# rpi.net
KiCad netlist of a schematic drawn in EAGLE
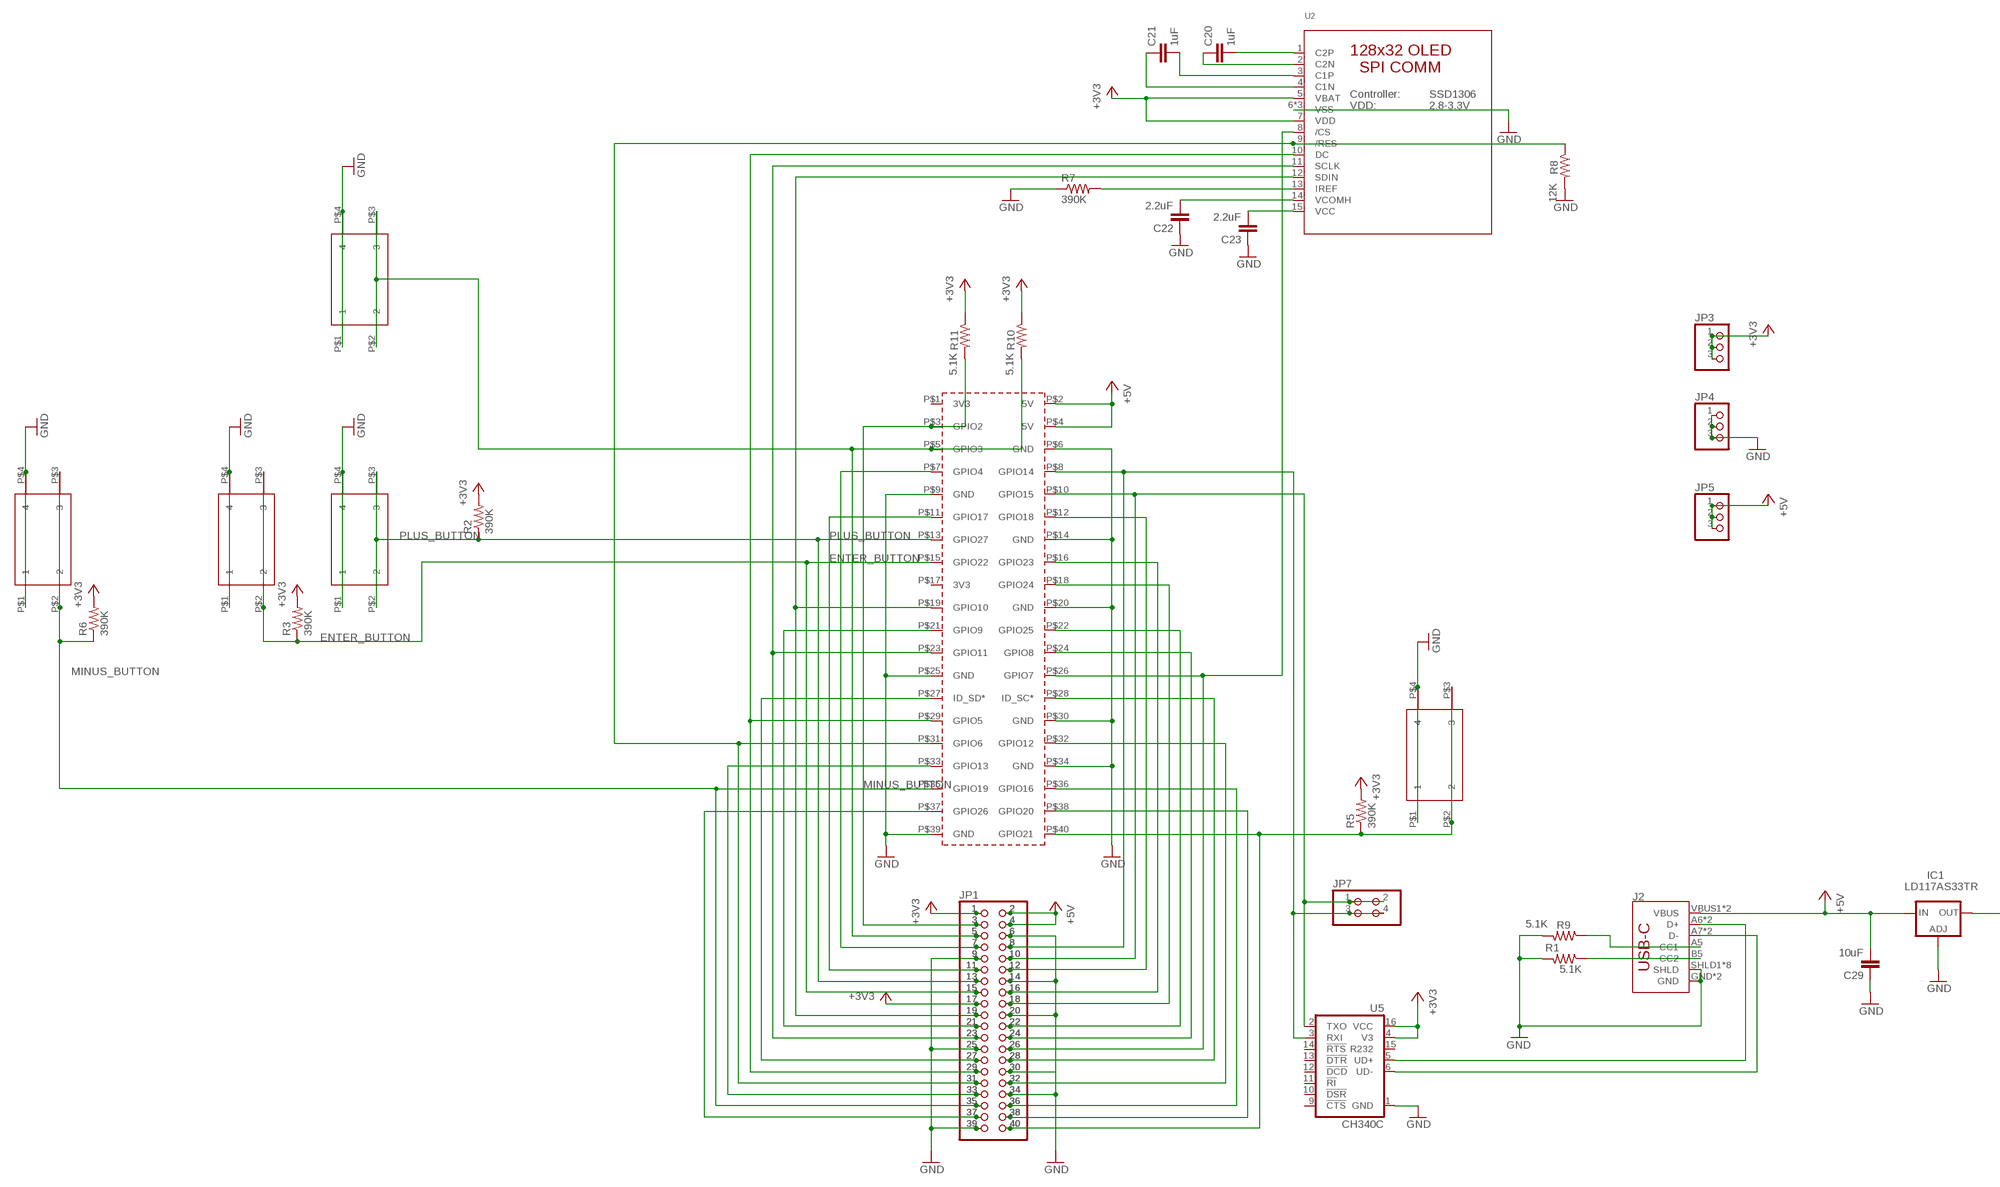
[diagram p0: schematic, sheet 1, part 1 of 2]
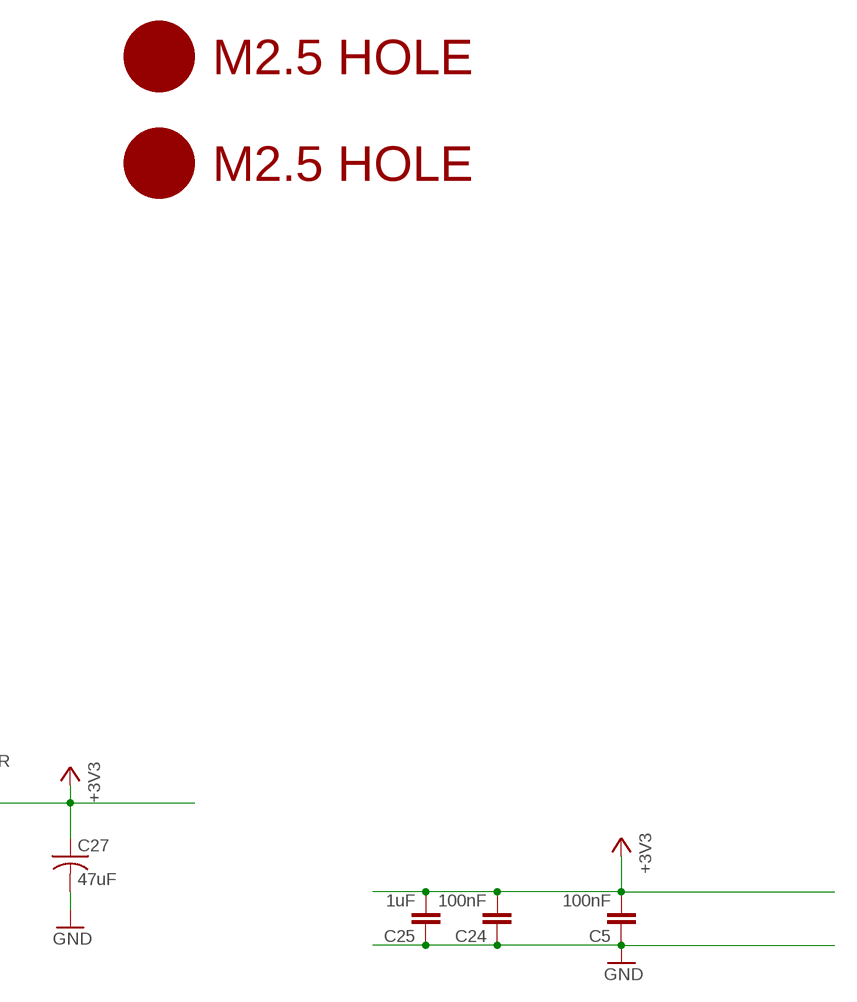
[diagram p1: schematic, sheet 1, part 2 of 2]

(export (version "E")
  (design (tool "Eeschema 10.0.6"))
  (components
    (comp (ref "C5")
      (value "100nF")
      (footprint "eagle-import:0805")
      (libsource (lib "eagle-import") (part "CAP0805"))
    )
    (comp (ref "C20")
      (value "1uF")
      (footprint "eagle-import:0805")
      (libsource (lib "eagle-import") (part "CAP0805"))
    )
    (comp (ref "C21")
      (value "1uF")
      (footprint "eagle-import:0805")
      (libsource (lib "eagle-import") (part "CAP0805"))
    )
    (comp (ref "C22")
      (value "2.2uF")
      (footprint "eagle-import:0805")
      (libsource (lib "eagle-import") (part "CAP0805"))
    )
    (comp (ref "C23")
      (value "2.2uF")
      (footprint "eagle-import:0805")
      (libsource (lib "eagle-import") (part "CAP0805"))
    )
    (comp (ref "C24")
      (value "100nF")
      (footprint "eagle-import:0805")
      (libsource (lib "eagle-import") (part "CAP0805"))
    )
    (comp (ref "C25")
      (value "1uF")
      (footprint "eagle-import:0805")
      (libsource (lib "eagle-import") (part "CAP0805"))
    )
    (comp (ref "C27")
      (value "47uF")
      (footprint "eagle-import:C1210")
      (libsource (lib "eagle-import") (part "C-USC1210"))
    )
    (comp (ref "C29")
      (value "10uF")
      (footprint "eagle-import:0805")
      (libsource (lib "eagle-import") (part "CAP0805"))
    )
    (comp (ref "IC1")
      (value "LD117AS33TR")
      (footprint "eagle-import:SOT223")
      (libsource (lib "eagle-import") (part "LD117A?S33TR"))
    )
    (comp (ref "J2")
      (value "USB_C16PIN")
      (footprint "eagle-import:USB-C-16P")
      (libsource (lib "eagle-import") (part "USB_C16PIN"))
    )
    (comp (ref "JP1")
      (value "PINHD-2X20-BIG")
      (footprint "eagle-import:2X20-BIG")
      (libsource (lib "eagle-import") (part "PINHD-2X20-BIG"))
    )
    (comp (ref "JP2")
      (value "PINHD-2X20-BIG")
      (footprint "eagle-import:2X20-BIG")
      (libsource (lib "eagle-import") (part "PINHD-2X20-BIG"))
    )
    (comp (ref "JP3")
      (value "PINHD-1X3")
      (footprint "eagle-import:1X03")
      (libsource (lib "eagle-import") (part "PINHD-1X3"))
    )
    (comp (ref "JP4")
      (value "PINHD-1X3")
      (footprint "eagle-import:1X03")
      (libsource (lib "eagle-import") (part "PINHD-1X3"))
    )
    (comp (ref "JP5")
      (value "PINHD-1X3")
      (footprint "eagle-import:1X03")
      (libsource (lib "eagle-import") (part "PINHD-1X3"))
    )
    (comp (ref "JP7")
      (value "PINHD-2X2")
      (footprint "eagle-import:2X02")
      (libsource (lib "eagle-import") (part "PINHD-2X2"))
    )
    (comp (ref "PCB1")
      (value "RPI3NO-CONNECTORS")
      (footprint "eagle-import:RPI3-NO-CONNECTORS")
      (libsource (lib "eagle-import") (part "RPI3NO-CONNECTORS"))
    )
    (comp (ref "R1")
      (value "5.1K")
      (footprint "eagle-import:0805")
      (libsource (lib "eagle-import") (part "joyAnalog_RESISTOR0805-RES"))
    )
    (comp (ref "R2")
      (value "390K")
      (footprint "eagle-import:0805")
      (libsource (lib "eagle-import") (part "RESISTOR0805-RES"))
    )
    (comp (ref "R3")
      (value "390K")
      (footprint "eagle-import:0805")
      (libsource (lib "eagle-import") (part "RESISTOR0805-RES"))
    )
    (comp (ref "R5")
      (value "390K")
      (footprint "eagle-import:0805")
      (libsource (lib "eagle-import") (part "RESISTOR0805-RES"))
    )
    (comp (ref "R6")
      (value "390K")
      (footprint "eagle-import:0805")
      (libsource (lib "eagle-import") (part "RESISTOR0805-RES"))
    )
    (comp (ref "R7")
      (value "390K")
      (footprint "eagle-import:0805")
      (libsource (lib "eagle-import") (part "RESISTOR0805-RES"))
    )
    (comp (ref "R8")
      (value "12K")
      (footprint "eagle-import:0805")
      (libsource (lib "eagle-import") (part "joyAnalog_RESISTOR0805-RES"))
    )
    (comp (ref "R9")
      (value "5.1K")
      (footprint "eagle-import:0805")
      (libsource (lib "eagle-import") (part "joyAnalog_RESISTOR0805-RES"))
    )
    (comp (ref "R10")
      (value "5.1K")
      (footprint "eagle-import:0805")
      (libsource (lib "eagle-import") (part "joyAnalog_RESISTOR0805-RES"))
    )
    (comp (ref "R11")
      (value "5.1K")
      (footprint "eagle-import:0805")
      (libsource (lib "eagle-import") (part "joyAnalog_RESISTOR0805-RES"))
    )
    (comp (ref "SW1")
      (value "324_SW")
      (footprint "eagle-import:342_SWICH_FOOT")
      (libsource (lib "eagle-import") (part "324_SW"))
    )
    (comp (ref "SW2")
      (value "324_SW")
      (footprint "eagle-import:342_SWICH_FOOT")
      (libsource (lib "eagle-import") (part "324_SW"))
    )
    (comp (ref "SW3")
      (value "324_SW")
      (footprint "eagle-import:342_SWICH_FOOT")
      (libsource (lib "eagle-import") (part "324_SW"))
    )
    (comp (ref "SW4")
      (value "324_SW")
      (footprint "eagle-import:342_SWICH_FOOT")
      (libsource (lib "eagle-import") (part "324_SW"))
    )
    (comp (ref "SW20")
      (value "324_SW")
      (footprint "eagle-import:342_SWICH_FOOT")
      (libsource (lib "eagle-import") (part "324_SW"))
    )
    (comp (ref "U$2")
      (value "M2.5HOLE")
      (footprint "eagle-import:M2.5HOLE")
      (libsource (lib "eagle-import") (part "M2.5HOLE"))
    )
    (comp (ref "U$3")
      (value "M2.5HOLE")
      (footprint "eagle-import:M2.5HOLE")
      (libsource (lib "eagle-import") (part "M2.5HOLE"))
    )
    (comp (ref "U2")
      (value "LUL_DISP_OLED_UG-2864HSWEG01")
      (footprint "eagle-import:LUL_UG-2864HSWEG01_1.3_WRAPAROUND")
      (libsource (lib "eagle-import") (part "LUL_DISP_OLED_UG-2864HSWEG01"))
    )
    (comp (ref "U5")
      (value "CH340C")
      (footprint "eagle-import:SO016")
      (libsource (lib "eagle-import") (part "CH340C"))
    )
  )
  (nets
    (net (code "1") (name "+3V3") (class "Default")
      (node (ref "C24") (pin "2") (pinfunction "2_2") (pintype "passive"))
      (node (ref "C25") (pin "2") (pinfunction "2_2") (pintype "passive"))
      (node (ref "C27") (pin "1") (pinfunction "1_1") (pintype "passive"))
      (node (ref "C5") (pin "2") (pinfunction "2_2") (pintype "passive"))
      (node (ref "IC1") (pin "4") (pinfunction "OUT_4") (pintype "passive"))
      (node (ref "JP1") (pin "1") (pinfunction "1_1") (pintype "passive"))
      (node (ref "JP1") (pin "17") (pinfunction "17_17") (pintype "passive"))
      (node (ref "JP2") (pin "1") (pinfunction "1_1") (pintype "passive"))
      (node (ref "JP2") (pin "17") (pinfunction "17_17") (pintype "passive"))
      (node (ref "JP3") (pin "1") (pinfunction "1_1") (pintype "passive"))
      (node (ref "JP3") (pin "2") (pinfunction "2_2") (pintype "passive"))
      (node (ref "JP3") (pin "3") (pinfunction "3_3") (pintype "passive"))
      (node (ref "R10") (pin "1") (pinfunction "1_1") (pintype "passive"))
      (node (ref "R11") (pin "1") (pinfunction "1_1") (pintype "passive"))
      (node (ref "R2") (pin "2") (pinfunction "2_2") (pintype "passive"))
      (node (ref "R3") (pin "2") (pinfunction "2_2") (pintype "passive"))
      (node (ref "R5") (pin "2") (pinfunction "2_2") (pintype "passive"))
      (node (ref "R6") (pin "2") (pinfunction "2_2") (pintype "passive"))
      (node (ref "U2") (pin "5") (pinfunction "VBAT_5") (pintype "input"))
      (node (ref "U2") (pin "7") (pinfunction "VDD_7") (pintype "power_in"))
      (node (ref "U5") (pin "16") (pinfunction "VCC_16") (pintype "bidirectional"))
      (node (ref "U5") (pin "4") (pinfunction "V3_4") (pintype "bidirectional"))
    )
    (net (code "2") (name "+5V") (class "Default")
      (node (ref "C29") (pin "2") (pinfunction "2_2") (pintype "passive"))
      (node (ref "IC1") (pin "3") (pinfunction "IN_3") (pintype "input"))
      (node (ref "J2") (pin "VBUS1") (pinfunction "VBUS_VBUS1") (pintype "bidirectional"))
      (node (ref "J2") (pin "VBUS2") (pinfunction "VBUS_VBUS2") (pintype "bidirectional"))
      (node (ref "JP1") (pin "2") (pinfunction "2_2") (pintype "passive"))
      (node (ref "JP1") (pin "4") (pinfunction "4_4") (pintype "passive"))
      (node (ref "JP2") (pin "2") (pinfunction "2_2") (pintype "passive"))
      (node (ref "JP2") (pin "4") (pinfunction "4_4") (pintype "passive"))
      (node (ref "JP5") (pin "1") (pinfunction "1_1") (pintype "passive"))
      (node (ref "JP5") (pin "2") (pinfunction "2_2") (pintype "passive"))
      (node (ref "JP5") (pin "3") (pinfunction "3_3") (pintype "passive"))
      (node (ref "PCB1") (pin "P$2") (pinfunction "5V_P$2") (pintype "bidirectional"))
      (node (ref "PCB1") (pin "P$4") (pinfunction "5V_P$4") (pintype "bidirectional"))
    )
    (net (code "3") (name "/ENTER_BUTTON") (class "Default")
      (node (ref "JP1") (pin "15") (pinfunction "15_15") (pintype "passive"))
      (node (ref "JP2") (pin "15") (pinfunction "15_15") (pintype "passive"))
      (node (ref "PCB1") (pin "P$15") (pinfunction "GPIO22_P$15") (pintype "bidirectional"))
      (node (ref "R3") (pin "1") (pinfunction "1_1") (pintype "passive"))
      (node (ref "SW20") (pin "P$2") (pinfunction "2_P$2") (pintype "bidirectional"))
      (node (ref "SW20") (pin "P$3") (pinfunction "3_P$3") (pintype "bidirectional"))
    )
    (net (code "4") (name "/MINUS_BUTTON") (class "Default")
      (node (ref "JP1") (pin "35") (pinfunction "35_35") (pintype "passive"))
      (node (ref "JP2") (pin "35") (pinfunction "35_35") (pintype "passive"))
      (node (ref "PCB1") (pin "P$35") (pinfunction "GPIO19_P$35") (pintype "bidirectional"))
      (node (ref "R6") (pin "1") (pinfunction "1_1") (pintype "passive"))
      (node (ref "SW4") (pin "P$2") (pinfunction "2_P$2") (pintype "bidirectional"))
      (node (ref "SW4") (pin "P$3") (pinfunction "3_P$3") (pintype "bidirectional"))
    )
    (net (code "5") (name "/PLUS_BUTTON") (class "Default")
      (node (ref "JP1") (pin "13") (pinfunction "13_13") (pintype "passive"))
      (node (ref "JP2") (pin "13") (pinfunction "13_13") (pintype "passive"))
      (node (ref "PCB1") (pin "P$13") (pinfunction "GPIO27_P$13") (pintype "bidirectional"))
      (node (ref "R2") (pin "1") (pinfunction "1_1") (pintype "passive"))
      (node (ref "SW1") (pin "P$2") (pinfunction "2_P$2") (pintype "bidirectional"))
      (node (ref "SW1") (pin "P$3") (pinfunction "3_P$3") (pintype "bidirectional"))
    )
    (net (code "6") (name "GND") (class "Default")
      (node (ref "C22") (pin "1") (pinfunction "1_1") (pintype "passive"))
      (node (ref "C23") (pin "1") (pinfunction "1_1") (pintype "passive"))
      (node (ref "C24") (pin "1") (pinfunction "1_1") (pintype "passive"))
      (node (ref "C25") (pin "1") (pinfunction "1_1") (pintype "passive"))
      (node (ref "C27") (pin "2") (pinfunction "2_2") (pintype "passive"))
      (node (ref "C29") (pin "1") (pinfunction "1_1") (pintype "passive"))
      (node (ref "C5") (pin "1") (pinfunction "1_1") (pintype "passive"))
      (node (ref "IC1") (pin "1") (pinfunction "ADJ_1") (pintype "input"))
      (node (ref "J2") (pin "GND") (pinfunction "GND_GND") (pintype "bidirectional"))
      (node (ref "J2") (pin "GND2") (pinfunction "GND_GND2") (pintype "bidirectional"))
      (node (ref "J2") (pin "SHLD1") (pinfunction "SHLD_SHLD1") (pintype "bidirectional"))
      (node (ref "J2") (pin "SHLD2") (pinfunction "SHLD_SHLD2") (pintype "bidirectional"))
      (node (ref "J2") (pin "SHLD3") (pinfunction "SHLD_SHLD3") (pintype "bidirectional"))
      (node (ref "J2") (pin "SHLD4") (pinfunction "SHLD_SHLD4") (pintype "bidirectional"))
      (node (ref "J2") (pin "SHLD5") (pinfunction "SHLD_SHLD5") (pintype "bidirectional"))
      (node (ref "J2") (pin "SHLD6") (pinfunction "SHLD_SHLD6") (pintype "bidirectional"))
      (node (ref "J2") (pin "SHLD7") (pinfunction "SHLD_SHLD7") (pintype "bidirectional"))
      (node (ref "J2") (pin "SHLD8") (pinfunction "SHLD_SHLD8") (pintype "bidirectional"))
      (node (ref "JP1") (pin "14") (pinfunction "14_14") (pintype "passive"))
      (node (ref "JP1") (pin "20") (pinfunction "20_20") (pintype "passive"))
      (node (ref "JP1") (pin "25") (pinfunction "25_25") (pintype "passive"))
      (node (ref "JP1") (pin "30") (pinfunction "30_30") (pintype "passive"))
      (node (ref "JP1") (pin "34") (pinfunction "34_34") (pintype "passive"))
      (node (ref "JP1") (pin "39") (pinfunction "39_39") (pintype "passive"))
      (node (ref "JP1") (pin "6") (pinfunction "6_6") (pintype "passive"))
      (node (ref "JP1") (pin "9") (pinfunction "9_9") (pintype "passive"))
      (node (ref "JP2") (pin "14") (pinfunction "14_14") (pintype "passive"))
      (node (ref "JP2") (pin "20") (pinfunction "20_20") (pintype "passive"))
      (node (ref "JP2") (pin "25") (pinfunction "25_25") (pintype "passive"))
      (node (ref "JP2") (pin "30") (pinfunction "30_30") (pintype "passive"))
      (node (ref "JP2") (pin "34") (pinfunction "34_34") (pintype "passive"))
      (node (ref "JP2") (pin "39") (pinfunction "39_39") (pintype "passive"))
      (node (ref "JP2") (pin "6") (pinfunction "6_6") (pintype "passive"))
      (node (ref "JP2") (pin "9") (pinfunction "9_9") (pintype "passive"))
      (node (ref "JP4") (pin "1") (pinfunction "1_1") (pintype "passive"))
      (node (ref "JP4") (pin "2") (pinfunction "2_2") (pintype "passive"))
      (node (ref "JP4") (pin "3") (pinfunction "3_3") (pintype "passive"))
      (node (ref "PCB1") (pin "P$14") (pinfunction "GND_P$14") (pintype "bidirectional"))
      (node (ref "PCB1") (pin "P$20") (pinfunction "GND_P$20") (pintype "bidirectional"))
      (node (ref "PCB1") (pin "P$25") (pinfunction "GND_P$25") (pintype "bidirectional"))
      (node (ref "PCB1") (pin "P$30") (pinfunction "GND_P$30") (pintype "bidirectional"))
      (node (ref "PCB1") (pin "P$34") (pinfunction "GND_P$34") (pintype "bidirectional"))
      (node (ref "PCB1") (pin "P$39") (pinfunction "GND_P$39") (pintype "bidirectional"))
      (node (ref "PCB1") (pin "P$6") (pinfunction "GND_P$6") (pintype "bidirectional"))
      (node (ref "PCB1") (pin "P$9") (pinfunction "GND_P$9") (pintype "bidirectional"))
      (node (ref "R1") (pin "2") (pinfunction "2_2") (pintype "passive"))
      (node (ref "R7") (pin "1") (pinfunction "1_1") (pintype "passive"))
      (node (ref "R8") (pin "2") (pinfunction "2_2") (pintype "passive"))
      (node (ref "R9") (pin "2") (pinfunction "2_2") (pintype "passive"))
      (node (ref "SW1") (pin "P$1") (pinfunction "1_P$1") (pintype "bidirectional"))
      (node (ref "SW1") (pin "P$4") (pinfunction "4_P$4") (pintype "bidirectional"))
      (node (ref "SW2") (pin "P$1") (pinfunction "1_P$1") (pintype "bidirectional"))
      (node (ref "SW2") (pin "P$4") (pinfunction "4_P$4") (pintype "bidirectional"))
      (node (ref "SW20") (pin "P$1") (pinfunction "1_P$1") (pintype "bidirectional"))
      (node (ref "SW20") (pin "P$4") (pinfunction "4_P$4") (pintype "bidirectional"))
      (node (ref "SW3") (pin "P$1") (pinfunction "1_P$1") (pintype "bidirectional"))
      (node (ref "SW3") (pin "P$4") (pinfunction "4_P$4") (pintype "bidirectional"))
      (node (ref "SW4") (pin "P$1") (pinfunction "1_P$1") (pintype "bidirectional"))
      (node (ref "SW4") (pin "P$4") (pinfunction "4_P$4") (pintype "bidirectional"))
      (node (ref "U2") (pin "16") (pinfunction "VSS_16") (pintype "power_in"))
      (node (ref "U2") (pin "17") (pinfunction "VSS_17") (pintype "power_in"))
      (node (ref "U2") (pin "6") (pinfunction "VSS_6") (pintype "power_in"))
      (node (ref "U5") (pin "1") (pinfunction "GND_1") (pintype "bidirectional"))
    )
    (net (code "7") (name "Net-(J2-CC1)") (class "Default")
      (node (ref "J2") (pin "A5") (pinfunction "CC1_A5") (pintype "bidirectional"))
      (node (ref "R9") (pin "1") (pinfunction "1_1") (pintype "passive"))
    )
    (net (code "8") (name "Net-(J2-CC2)") (class "Default")
      (node (ref "J2") (pin "B5") (pinfunction "CC2_B5") (pintype "bidirectional"))
      (node (ref "R1") (pin "1") (pinfunction "1_1") (pintype "passive"))
    )
    (net (code "9") (name "Net-(PCB1-GPIO2)") (class "Default")
      (node (ref "JP1") (pin "3") (pinfunction "3_3") (pintype "passive"))
      (node (ref "JP2") (pin "3") (pinfunction "3_3") (pintype "passive"))
      (node (ref "PCB1") (pin "P$3") (pinfunction "GPIO2_P$3") (pintype "bidirectional"))
      (node (ref "R11") (pin "2") (pinfunction "2_2") (pintype "passive"))
    )
    (net (code "10") (name "Net-(PCB1-GPIO3)") (class "Default")
      (node (ref "JP1") (pin "5") (pinfunction "5_5") (pintype "passive"))
      (node (ref "JP2") (pin "5") (pinfunction "5_5") (pintype "passive"))
      (node (ref "PCB1") (pin "P$5") (pinfunction "GPIO3_P$5") (pintype "bidirectional"))
      (node (ref "R10") (pin "2") (pinfunction "2_2") (pintype "passive"))
      (node (ref "SW2") (pin "P$2") (pinfunction "2_P$2") (pintype "bidirectional"))
      (node (ref "SW2") (pin "P$3") (pinfunction "3_P$3") (pintype "bidirectional"))
    )
    (net (code "11") (name "Net-(PCB1-GPIO4)") (class "Default")
      (node (ref "JP1") (pin "7") (pinfunction "7_7") (pintype "passive"))
      (node (ref "JP2") (pin "7") (pinfunction "7_7") (pintype "passive"))
      (node (ref "PCB1") (pin "P$7") (pinfunction "GPIO4_P$7") (pintype "bidirectional"))
    )
    (net (code "12") (name "Net-(PCB1-GPIO5)") (class "Default")
      (node (ref "JP1") (pin "29") (pinfunction "29_29") (pintype "passive"))
      (node (ref "JP2") (pin "29") (pinfunction "29_29") (pintype "passive"))
      (node (ref "PCB1") (pin "P$29") (pinfunction "GPIO5_P$29") (pintype "bidirectional"))
      (node (ref "U2") (pin "10") (pinfunction "DC_10") (pintype "input"))
    )
    (net (code "13") (name "Net-(PCB1-GPIO6)") (class "Default")
      (node (ref "JP1") (pin "31") (pinfunction "31_31") (pintype "passive"))
      (node (ref "JP2") (pin "31") (pinfunction "31_31") (pintype "passive"))
      (node (ref "PCB1") (pin "P$31") (pinfunction "GPIO6_P$31") (pintype "bidirectional"))
      (node (ref "R8") (pin "1") (pinfunction "1_1") (pintype "passive"))
      (node (ref "U2") (pin "9") (pinfunction "/RES_9") (pintype "input"))
    )
    (net (code "14") (name "Net-(PCB1-GPIO7)") (class "Default")
      (node (ref "JP1") (pin "26") (pinfunction "26_26") (pintype "passive"))
      (node (ref "JP2") (pin "26") (pinfunction "26_26") (pintype "passive"))
      (node (ref "PCB1") (pin "P$26") (pinfunction "GPIO7_P$26") (pintype "bidirectional"))
      (node (ref "U2") (pin "8") (pinfunction "/CS_8") (pintype "input"))
    )
    (net (code "15") (name "Net-(PCB1-GPIO8)") (class "Default")
      (node (ref "JP1") (pin "24") (pinfunction "24_24") (pintype "passive"))
      (node (ref "JP2") (pin "24") (pinfunction "24_24") (pintype "passive"))
      (node (ref "PCB1") (pin "P$24") (pinfunction "GPIO8_P$24") (pintype "bidirectional"))
    )
    (net (code "16") (name "Net-(PCB1-GPIO9)") (class "Default")
      (node (ref "JP1") (pin "21") (pinfunction "21_21") (pintype "passive"))
      (node (ref "JP2") (pin "21") (pinfunction "21_21") (pintype "passive"))
      (node (ref "PCB1") (pin "P$21") (pinfunction "GPIO9_P$21") (pintype "bidirectional"))
    )
    (net (code "17") (name "Net-(PCB1-GPIO10)") (class "Default")
      (node (ref "JP1") (pin "19") (pinfunction "19_19") (pintype "passive"))
      (node (ref "JP2") (pin "19") (pinfunction "19_19") (pintype "passive"))
      (node (ref "PCB1") (pin "P$19") (pinfunction "GPIO10_P$19") (pintype "bidirectional"))
      (node (ref "U2") (pin "12") (pinfunction "SDIN_12") (pintype "bidirectional"))
    )
    (net (code "18") (name "Net-(PCB1-GPIO11)") (class "Default")
      (node (ref "JP1") (pin "23") (pinfunction "23_23") (pintype "passive"))
      (node (ref "JP2") (pin "23") (pinfunction "23_23") (pintype "passive"))
      (node (ref "PCB1") (pin "P$23") (pinfunction "GPIO11_P$23") (pintype "bidirectional"))
      (node (ref "U2") (pin "11") (pinfunction "SCLK_11") (pintype "bidirectional"))
    )
    (net (code "19") (name "Net-(PCB1-GPIO12)") (class "Default")
      (node (ref "JP1") (pin "32") (pinfunction "32_32") (pintype "passive"))
      (node (ref "JP2") (pin "32") (pinfunction "32_32") (pintype "passive"))
      (node (ref "PCB1") (pin "P$32") (pinfunction "GPIO12_P$32") (pintype "bidirectional"))
    )
    (net (code "20") (name "Net-(PCB1-GPIO13)") (class "Default")
      (node (ref "JP1") (pin "33") (pinfunction "33_33") (pintype "passive"))
      (node (ref "JP2") (pin "33") (pinfunction "33_33") (pintype "passive"))
      (node (ref "PCB1") (pin "P$33") (pinfunction "GPIO13_P$33") (pintype "bidirectional"))
    )
    (net (code "21") (name "Net-(PCB1-GPIO14)") (class "Default")
      (node (ref "JP1") (pin "8") (pinfunction "8_8") (pintype "passive"))
      (node (ref "JP2") (pin "8") (pinfunction "8_8") (pintype "passive"))
      (node (ref "JP7") (pin "3") (pinfunction "3_3") (pintype "passive"))
      (node (ref "JP7") (pin "4") (pinfunction "4_4") (pintype "passive"))
      (node (ref "PCB1") (pin "P$8") (pinfunction "GPIO14_P$8") (pintype "bidirectional"))
      (node (ref "U5") (pin "3") (pinfunction "RXI_3") (pintype "bidirectional"))
    )
    (net (code "22") (name "Net-(PCB1-GPIO15)") (class "Default")
      (node (ref "JP1") (pin "10") (pinfunction "10_10") (pintype "passive"))
      (node (ref "JP2") (pin "10") (pinfunction "10_10") (pintype "passive"))
      (node (ref "JP7") (pin "1") (pinfunction "1_1") (pintype "passive"))
      (node (ref "JP7") (pin "2") (pinfunction "2_2") (pintype "passive"))
      (node (ref "PCB1") (pin "P$10") (pinfunction "GPIO15_P$10") (pintype "bidirectional"))
      (node (ref "U5") (pin "2") (pinfunction "TXO_2") (pintype "bidirectional"))
    )
    (net (code "23") (name "Net-(PCB1-GPIO16)") (class "Default")
      (node (ref "JP1") (pin "36") (pinfunction "36_36") (pintype "passive"))
      (node (ref "JP2") (pin "36") (pinfunction "36_36") (pintype "passive"))
      (node (ref "PCB1") (pin "P$36") (pinfunction "GPIO16_P$36") (pintype "bidirectional"))
    )
    (net (code "24") (name "Net-(PCB1-GPIO17)") (class "Default")
      (node (ref "JP1") (pin "11") (pinfunction "11_11") (pintype "passive"))
      (node (ref "JP2") (pin "11") (pinfunction "11_11") (pintype "passive"))
      (node (ref "PCB1") (pin "P$11") (pinfunction "GPIO17_P$11") (pintype "bidirectional"))
    )
    (net (code "25") (name "Net-(PCB1-GPIO18)") (class "Default")
      (node (ref "JP1") (pin "12") (pinfunction "12_12") (pintype "passive"))
      (node (ref "JP2") (pin "12") (pinfunction "12_12") (pintype "passive"))
      (node (ref "PCB1") (pin "P$12") (pinfunction "GPIO18_P$12") (pintype "bidirectional"))
    )
    (net (code "26") (name "Net-(PCB1-GPIO20)") (class "Default")
      (node (ref "JP1") (pin "38") (pinfunction "38_38") (pintype "passive"))
      (node (ref "JP2") (pin "38") (pinfunction "38_38") (pintype "passive"))
      (node (ref "PCB1") (pin "P$38") (pinfunction "GPIO20_P$38") (pintype "bidirectional"))
    )
    (net (code "27") (name "Net-(PCB1-GPIO21)") (class "Default")
      (node (ref "JP1") (pin "40") (pinfunction "40_40") (pintype "passive"))
      (node (ref "JP2") (pin "40") (pinfunction "40_40") (pintype "passive"))
      (node (ref "PCB1") (pin "P$40") (pinfunction "GPIO21_P$40") (pintype "bidirectional"))
      (node (ref "R5") (pin "1") (pinfunction "1_1") (pintype "passive"))
      (node (ref "SW3") (pin "P$2") (pinfunction "2_P$2") (pintype "bidirectional"))
      (node (ref "SW3") (pin "P$3") (pinfunction "3_P$3") (pintype "bidirectional"))
    )
    (net (code "28") (name "Net-(PCB1-GPIO23)") (class "Default")
      (node (ref "JP1") (pin "16") (pinfunction "16_16") (pintype "passive"))
      (node (ref "JP2") (pin "16") (pinfunction "16_16") (pintype "passive"))
      (node (ref "PCB1") (pin "P$16") (pinfunction "GPIO23_P$16") (pintype "bidirectional"))
    )
    (net (code "29") (name "Net-(PCB1-GPIO24)") (class "Default")
      (node (ref "JP1") (pin "18") (pinfunction "18_18") (pintype "passive"))
      (node (ref "JP2") (pin "18") (pinfunction "18_18") (pintype "passive"))
      (node (ref "PCB1") (pin "P$18") (pinfunction "GPIO24_P$18") (pintype "bidirectional"))
    )
    (net (code "30") (name "Net-(PCB1-GPIO25)") (class "Default")
      (node (ref "JP1") (pin "22") (pinfunction "22_22") (pintype "passive"))
      (node (ref "JP2") (pin "22") (pinfunction "22_22") (pintype "passive"))
      (node (ref "PCB1") (pin "P$22") (pinfunction "GPIO25_P$22") (pintype "bidirectional"))
    )
    (net (code "31") (name "Net-(PCB1-GPIO26)") (class "Default")
      (node (ref "JP1") (pin "37") (pinfunction "37_37") (pintype "passive"))
      (node (ref "JP2") (pin "37") (pinfunction "37_37") (pintype "passive"))
      (node (ref "PCB1") (pin "P$37") (pinfunction "GPIO26_P$37") (pintype "bidirectional"))
    )
    (net (code "32") (name "Net-(PCB1-ID_SC*)") (class "Default")
      (node (ref "JP1") (pin "28") (pinfunction "28_28") (pintype "passive"))
      (node (ref "JP2") (pin "28") (pinfunction "28_28") (pintype "passive"))
      (node (ref "PCB1") (pin "P$28") (pinfunction "ID_SC*_P$28") (pintype "bidirectional"))
    )
    (net (code "33") (name "Net-(PCB1-ID_SD*)") (class "Default")
      (node (ref "JP1") (pin "27") (pinfunction "27_27") (pintype "passive"))
      (node (ref "JP2") (pin "27") (pinfunction "27_27") (pintype "passive"))
      (node (ref "PCB1") (pin "P$27") (pinfunction "ID_SD*_P$27") (pintype "bidirectional"))
    )
    (net (code "34") (name "Net-(U2-C1N)") (class "Default")
      (node (ref "C21") (pin "1") (pinfunction "1_1") (pintype "passive"))
      (node (ref "U2") (pin "4") (pinfunction "C1N_4") (pintype "input"))
    )
    (net (code "35") (name "Net-(U2-C1P)") (class "Default")
      (node (ref "C21") (pin "2") (pinfunction "2_2") (pintype "passive"))
      (node (ref "U2") (pin "3") (pinfunction "C1P_3") (pintype "input"))
    )
    (net (code "36") (name "Net-(U2-C2N)") (class "Default")
      (node (ref "C20") (pin "1") (pinfunction "1_1") (pintype "passive"))
      (node (ref "U2") (pin "2") (pinfunction "C2N_2") (pintype "input"))
    )
    (net (code "37") (name "Net-(U2-C2P)") (class "Default")
      (node (ref "C20") (pin "2") (pinfunction "2_2") (pintype "passive"))
      (node (ref "U2") (pin "1") (pinfunction "C2P_1") (pintype "input"))
    )
    (net (code "38") (name "Net-(U2-IREF)") (class "Default")
      (node (ref "R7") (pin "2") (pinfunction "2_2") (pintype "passive"))
      (node (ref "U2") (pin "13") (pinfunction "IREF_13") (pintype "input"))
    )
    (net (code "39") (name "Net-(U2-VCC)") (class "Default")
      (node (ref "C23") (pin "2") (pinfunction "2_2") (pintype "passive"))
      (node (ref "U2") (pin "15") (pinfunction "VCC_15") (pintype "power_in"))
    )
    (net (code "40") (name "Net-(U2-VCOMH)") (class "Default")
      (node (ref "C22") (pin "2") (pinfunction "2_2") (pintype "passive"))
      (node (ref "U2") (pin "14") (pinfunction "VCOMH_14") (pintype "output"))
    )
    (net (code "41") (name "Net-(U5-UD+)") (class "Default")
      (node (ref "J2") (pin "A6") (pinfunction "D+_A6") (pintype "bidirectional"))
      (node (ref "J2") (pin "B6") (pinfunction "D+_B6") (pintype "bidirectional"))
      (node (ref "U5") (pin "5") (pinfunction "UD+_5") (pintype "bidirectional"))
    )
    (net (code "42") (name "Net-(U5-UD-)") (class "Default")
      (node (ref "J2") (pin "A7") (pinfunction "D-_A7") (pintype "bidirectional"))
      (node (ref "J2") (pin "B7") (pinfunction "D-_B7") (pintype "bidirectional"))
      (node (ref "U5") (pin "6") (pinfunction "UD-_6") (pintype "bidirectional"))
    )
    (net (code "43") (name "unconnected-(PCB1-3V3-PadP$1)") (class "Default")
      (node (ref "PCB1") (pin "P$1") (pinfunction "3V3_P$1") (pintype "bidirectional"))
    )
    (net (code "44") (name "unconnected-(PCB1-3V3-PadP$17)") (class "Default")
      (node (ref "PCB1") (pin "P$17") (pinfunction "3V3_P$17") (pintype "bidirectional"))
    )
    (net (code "45") (name "unconnected-(U5-R232-Pad15)") (class "Default")
      (node (ref "U5") (pin "15") (pinfunction "R232_15") (pintype "bidirectional"))
    )
    (net (code "46") (name "unconnected-(U5-~{CTS}-Pad9)") (class "Default")
      (node (ref "U5") (pin "9") (pinfunction "~{CTS}_9") (pintype "bidirectional"))
    )
    (net (code "47") (name "unconnected-(U5-~{DCD}-Pad12)") (class "Default")
      (node (ref "U5") (pin "12") (pinfunction "~{DCD}_12") (pintype "bidirectional"))
    )
    (net (code "48") (name "unconnected-(U5-~{DSR}-Pad10)") (class "Default")
      (node (ref "U5") (pin "10") (pinfunction "~{DSR}_10") (pintype "bidirectional"))
    )
    (net (code "49") (name "unconnected-(U5-~{DTR}-Pad13)") (class "Default")
      (node (ref "U5") (pin "13") (pinfunction "~{DTR}_13") (pintype "bidirectional"))
    )
    (net (code "50") (name "unconnected-(U5-~{RI}-Pad11)") (class "Default")
      (node (ref "U5") (pin "11") (pinfunction "~{RI}_11") (pintype "bidirectional"))
    )
    (net (code "51") (name "unconnected-(U5-~{RTS}-Pad14)") (class "Default")
      (node (ref "U5") (pin "14") (pinfunction "~{RTS}_14") (pintype "bidirectional"))
    )
  )
)
